# AST1018.net
KiCad netlist of a schematic drawn in EAGLE
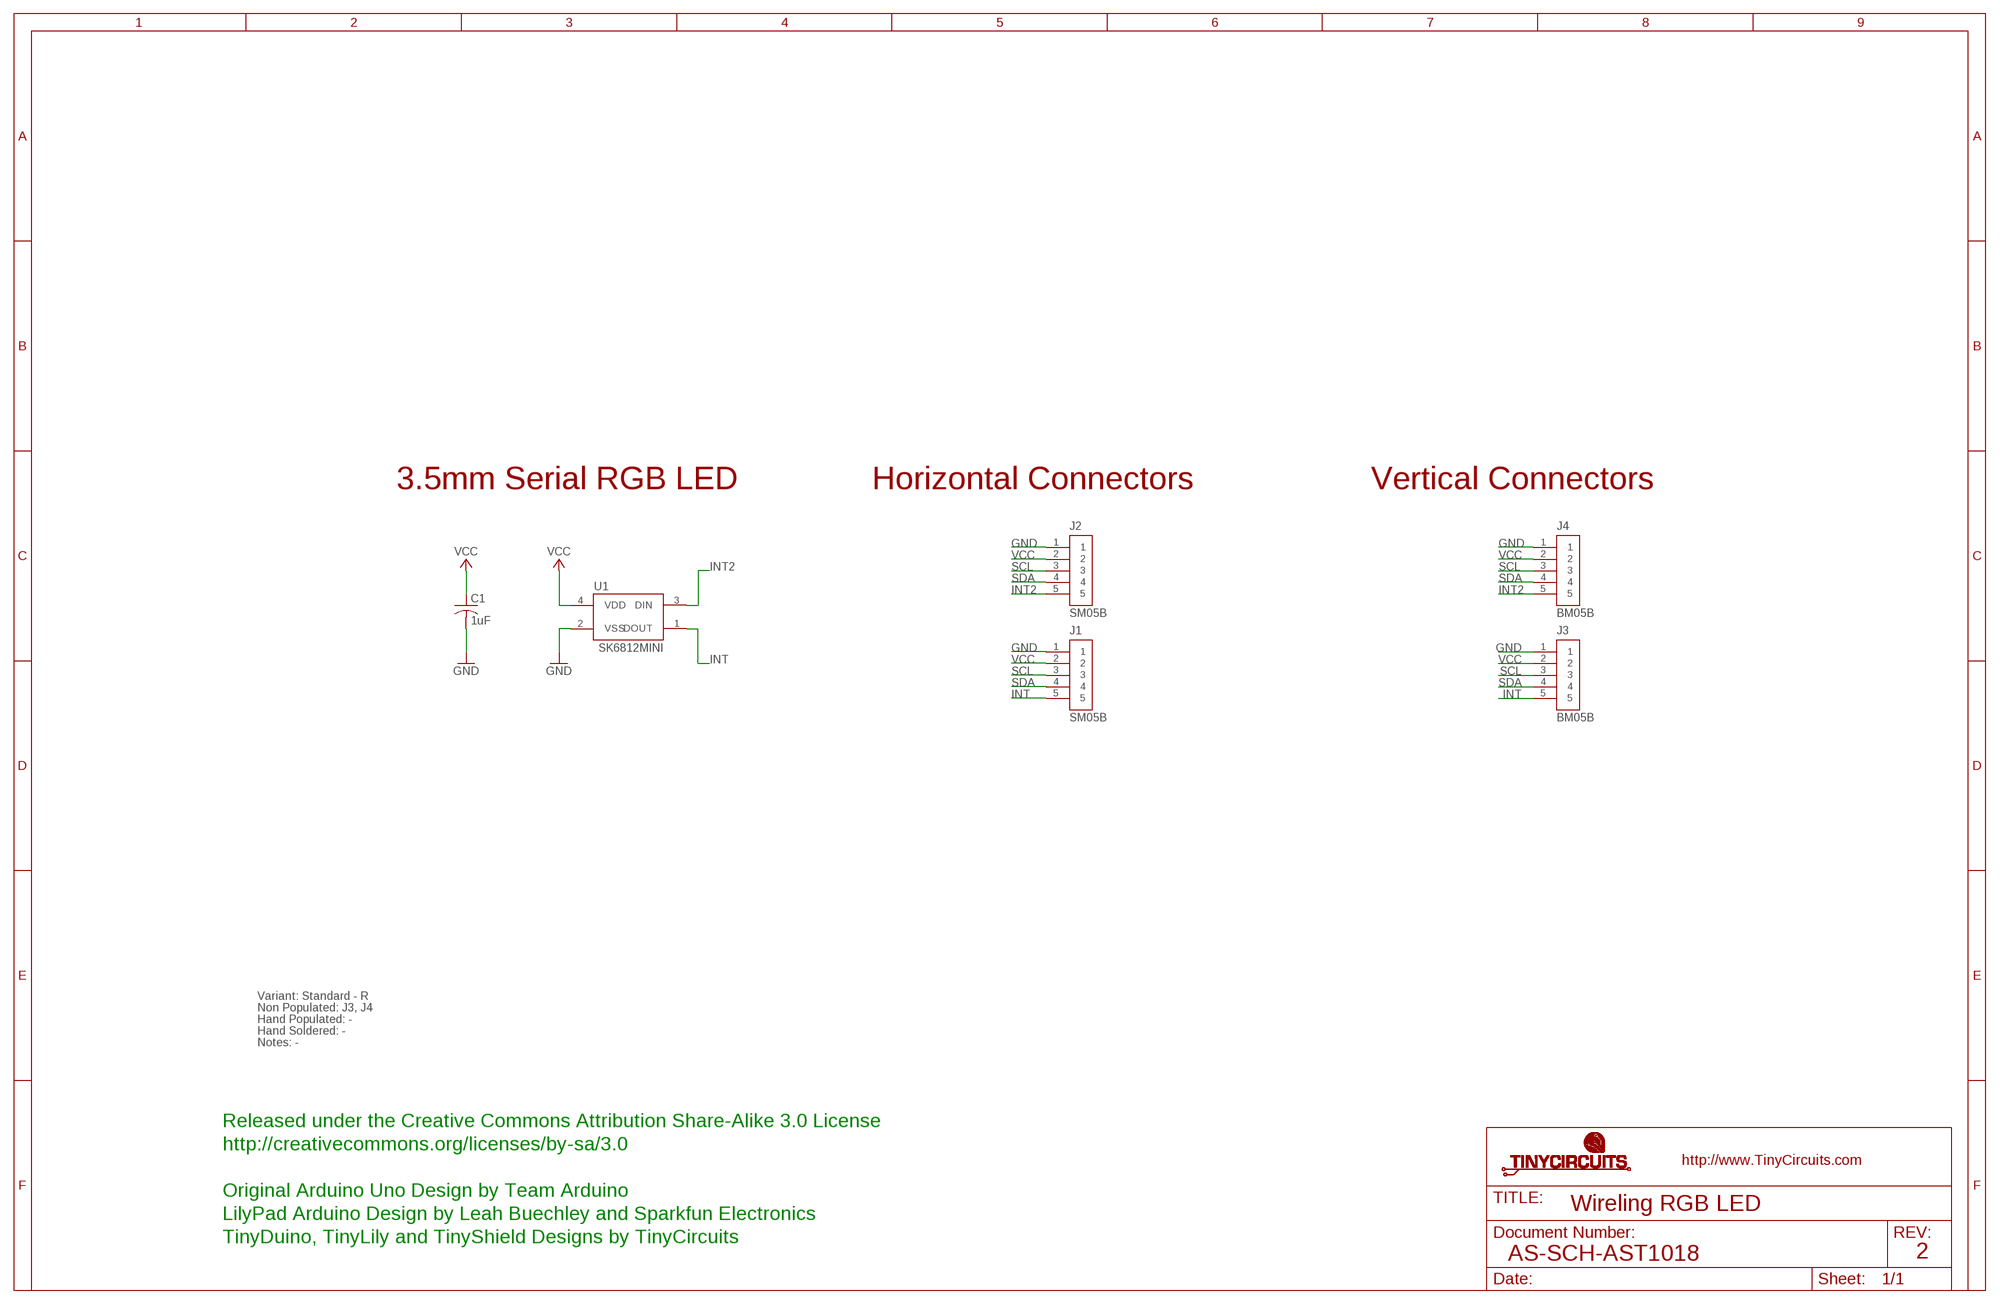
[diagram p0: schematic, sheet 1]

(export (version "E")
  (design (tool "Eeschema 10.0.6"))
  (components
    (comp (ref "C1")
      (value "1uF")
      (footprint "eagle-import:C0603")
      (fields (field (name "PARTNO") "AS-ITM-00410"))
      (libsource (lib "eagle-import") (part "AS-ITM-00410"))
    )
    (comp (ref "J1")
      (value "SM05B")
      (footprint "eagle-import:JST_SH_5X1_EDGE")
      (fields (field (name "PARTNO") "AS-ITM-00340"))
      (libsource (lib "eagle-import") (part "AS-ITM-00340EDGE"))
    )
    (comp (ref "J2")
      (value "SM05B")
      (footprint "eagle-import:JST_SH_5X1_EDGE")
      (fields (field (name "PARTNO") "AS-ITM-00340"))
      (libsource (lib "eagle-import") (part "AS-ITM-00340EDGE"))
    )
    (comp (ref "J3")
      (value "BM05B")
      (footprint "eagle-import:JST_SH_5X1_VERT")
      (fields (field (name "PARTNO") "AS-ITM-00391"))
      (libsource (lib "eagle-import") (part "AS-ITM-00391"))
    )
    (comp (ref "J4")
      (value "BM05B")
      (footprint "eagle-import:JST_SH_5X1_VERT")
      (fields (field (name "PARTNO") "AS-ITM-00391") (field (name "PARTNO_1") "AS-ITM-00391"))
      (libsource (lib "eagle-import") (part "AS-ITM-00391"))
    )
    (comp (ref "U1")
      (value "SK6812MINI")
      (footprint "eagle-import:SK6812MINI")
      (fields (field (name "PARTNO") "AS-ITM-00343"))
      (libsource (lib "eagle-import") (part "AS-ITM-00343"))
    )
  )
  (nets
    (net (code "1") (name "/INT") (class "Default")
      (node (ref "J1") (pin "5") (pinfunction "5_5") (pintype "bidirectional"))
      (node (ref "J3") (pin "5") (pinfunction "5_5") (pintype "bidirectional"))
      (node (ref "U1") (pin "1") (pinfunction "DOUT_1") (pintype "bidirectional"))
    )
    (net (code "2") (name "/INT2") (class "Default")
      (node (ref "J2") (pin "5") (pinfunction "5_5") (pintype "bidirectional"))
      (node (ref "J4") (pin "5") (pinfunction "5_5") (pintype "bidirectional"))
      (node (ref "U1") (pin "3") (pinfunction "DIN_3") (pintype "bidirectional"))
    )
    (net (code "3") (name "/SCL") (class "Default")
      (node (ref "J1") (pin "3") (pinfunction "3_3") (pintype "bidirectional"))
      (node (ref "J2") (pin "3") (pinfunction "3_3") (pintype "bidirectional"))
      (node (ref "J3") (pin "3") (pinfunction "3_3") (pintype "bidirectional"))
      (node (ref "J4") (pin "3") (pinfunction "3_3") (pintype "bidirectional"))
    )
    (net (code "4") (name "/SDA") (class "Default")
      (node (ref "J1") (pin "4") (pinfunction "4_4") (pintype "bidirectional"))
      (node (ref "J2") (pin "4") (pinfunction "4_4") (pintype "bidirectional"))
      (node (ref "J3") (pin "4") (pinfunction "4_4") (pintype "bidirectional"))
      (node (ref "J4") (pin "4") (pinfunction "4_4") (pintype "bidirectional"))
    )
    (net (code "5") (name "GND") (class "Default")
      (node (ref "C1") (pin "2") (pinfunction "2_2") (pintype "passive"))
      (node (ref "J1") (pin "1") (pinfunction "1_1") (pintype "bidirectional"))
      (node (ref "J2") (pin "1") (pinfunction "1_1") (pintype "bidirectional"))
      (node (ref "J3") (pin "1") (pinfunction "1_1") (pintype "bidirectional"))
      (node (ref "J4") (pin "1") (pinfunction "1_1") (pintype "bidirectional"))
      (node (ref "U1") (pin "2") (pinfunction "VSS_2") (pintype "bidirectional"))
    )
    (net (code "6") (name "VCC") (class "Default")
      (node (ref "C1") (pin "1") (pinfunction "1_1") (pintype "passive"))
      (node (ref "J1") (pin "2") (pinfunction "2_2") (pintype "bidirectional"))
      (node (ref "J2") (pin "2") (pinfunction "2_2") (pintype "bidirectional"))
      (node (ref "J3") (pin "2") (pinfunction "2_2") (pintype "bidirectional"))
      (node (ref "J4") (pin "2") (pinfunction "2_2") (pintype "bidirectional"))
      (node (ref "U1") (pin "4") (pinfunction "VDD_4") (pintype "bidirectional"))
    )
  )
)
